# ADC.net
KiCad netlist of a schematic drawn in Altium Designer
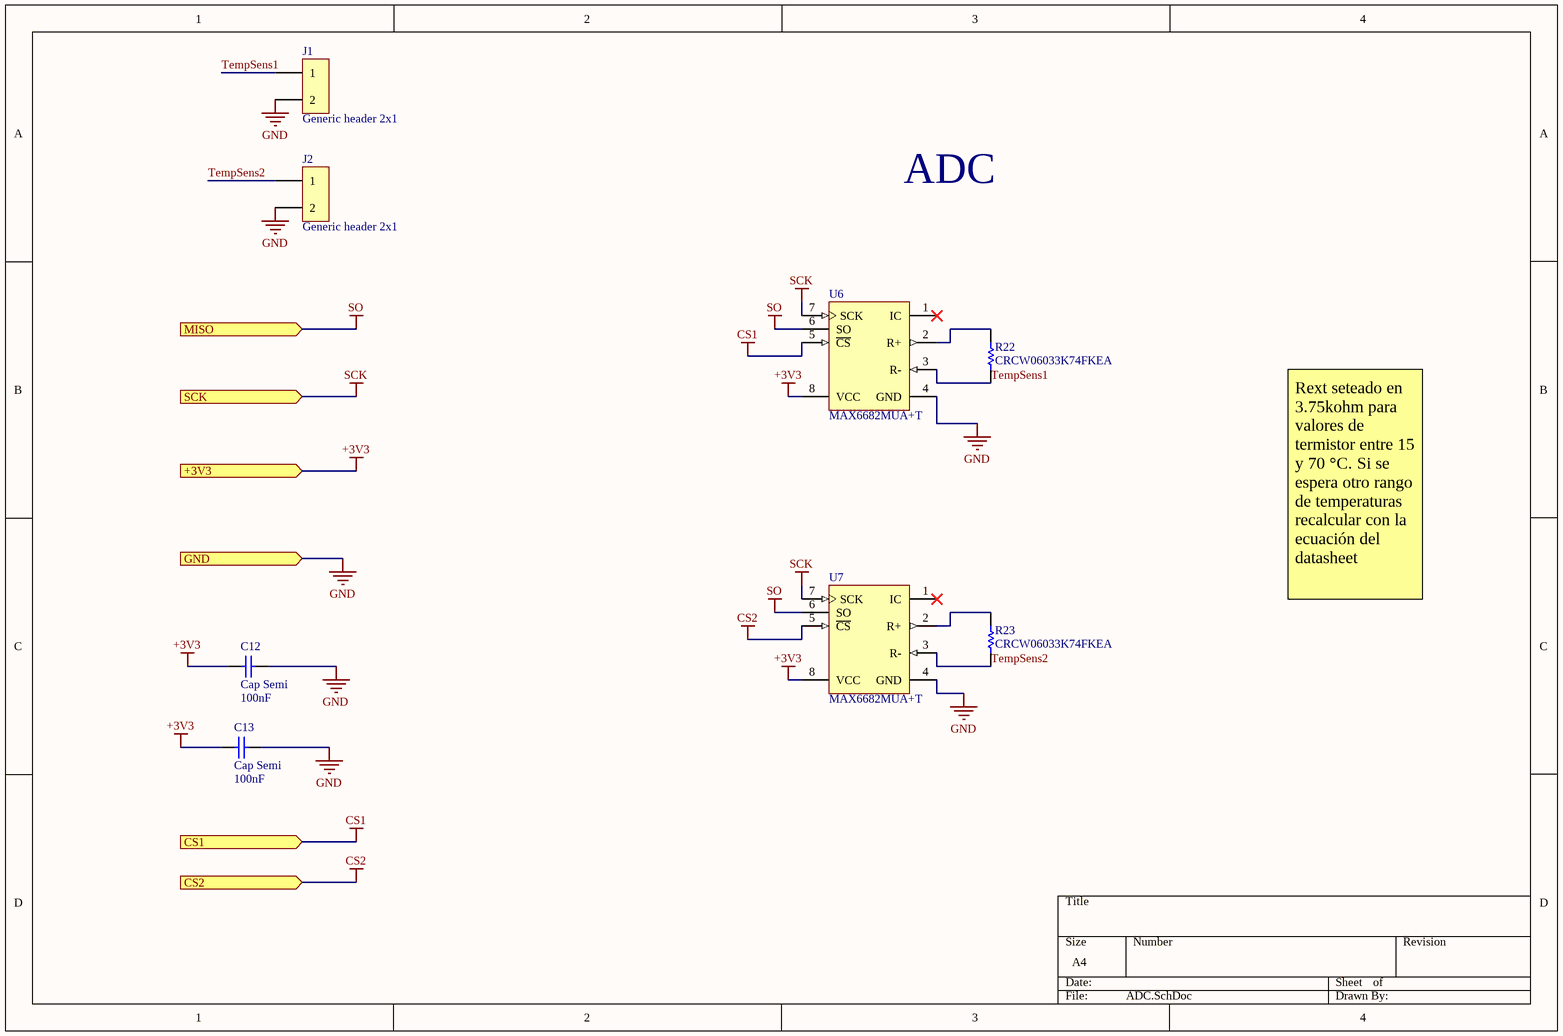
[diagram p0: ADC.SchDoc]

(export (version "E")
  (design (tool "Eeschema 10.0.6"))
  (components
    (comp (ref "C12")
      (value "Cap Semi")
      (footprint "1608[0603]")
      (description "Capacitor (Semiconductor SIM Model)")
      (fields
        (field (name "ALTIUM_VALUE") "100nF")
        (field (name "MANUFACTURER") "Taiyo Yuden")
        (field (name "MANUFACTURER PART NUMBER") "UMK107B104KAHT")
        (field (name "PUBLISHER") "Altium Limited")
      )
      (libsource (lib "Miscellaneous Devices") (part "Cap Semi"))
    )
    (comp (ref "C13")
      (value "Cap Semi")
      (footprint "1608[0603]")
      (description "Capacitor (Semiconductor SIM Model)")
      (fields
        (field (name "ALTIUM_VALUE") "100nF")
        (field (name "MANUFACTURER") "Taiyo Yuden")
        (field (name "MANUFACTURER PART NUMBER") "UMK107B104KAHT")
        (field (name "PUBLISHER") "Altium Limited")
      )
      (libsource (lib "Miscellaneous Devices") (part "Cap Semi"))
    )
    (comp (ref "J1")
      (value "Generic header 2x1")
      (footprint "JST-2x1")
      (description "Generic Header 2pos, 1 row, 2.54 pitch")
      (fields
        (field (name "MANUFACTURER") "CJT(Changjiang Connectors)")
        (field (name "MANUFACTURER PART NUMBER") "A2547WV-2P")
      )
      (libsource (lib "IoWLabsConnectors") (part "Header - 2x1"))
    )
    (comp (ref "J2")
      (value "Generic header 2x1")
      (footprint "JST-2x1")
      (description "Generic Header 2pos, 1 row, 2.54 pitch")
      (fields
        (field (name "MANUFACTURER") "CJT(Changjiang Connectors)")
        (field (name "MANUFACTURER PART NUMBER") "A2547WV-2P")
      )
      (libsource (lib "IoWLabsConnectors") (part "Header - 2x1"))
    )
    (comp (ref "R22")
      (value "CRCW06033K74FKEA")
      (footprint "RESC1609X50X30LL10T20")
      (fields (field (name "MANUFACTURER") "Vishay Dale"))
      (libsource (lib "Altium Content Vault") (part "RES"))
    )
    (comp (ref "R23")
      (value "CRCW06033K74FKEA")
      (footprint "RESC1609X50X30LL10T20")
      (fields (field (name "MANUFACTURER") "Vishay Dale"))
      (libsource (lib "Altium Content Vault") (part "RES"))
    )
    (comp (ref "U6")
      (value "MAX6682MUA+T")
      (footprint "MAXM-U8+1_L")
      (fields (field (name "GENERIC PART NUMBER") "MAX6682"))
      (libsource (lib "Altium Content Vault") (part "MAX6682-U8X1"))
    )
    (comp (ref "U7")
      (value "MAX6682MUA+T")
      (footprint "MAXM-U8+1_L")
      (fields (field (name "GENERIC PART NUMBER") "MAX6682"))
      (libsource (lib "Altium Content Vault") (part "MAX6682-U8X1"))
    )
  )
  (nets
    (net (code "1") (name "+3V3") (class "Default")
      (node (ref "C12") (pin "2") (pinfunction "2_2") (pintype "passive"))
      (node (ref "C13") (pin "2") (pinfunction "2_2") (pintype "passive"))
      (node (ref "U6") (pin "8") (pinfunction "VCC_8") (pintype "power_in"))
      (node (ref "U7") (pin "8") (pinfunction "VCC_8") (pintype "power_in"))
    )
    (net (code "2") (name "/TempSens1") (class "Default")
      (node (ref "J1") (pin "1") (pinfunction "1_1") (pintype "passive"))
      (node (ref "R22") (pin "1") (pinfunction "1_1") (pintype "passive"))
      (node (ref "U6") (pin "3") (pinfunction "R-_3") (pintype "input"))
    )
    (net (code "3") (name "/TempSens2") (class "Default")
      (node (ref "J2") (pin "1") (pinfunction "1_1") (pintype "passive"))
      (node (ref "R23") (pin "1") (pinfunction "1_1") (pintype "passive"))
      (node (ref "U7") (pin "3") (pinfunction "R-_3") (pintype "input"))
    )
    (net (code "4") (name "CS1") (class "Default")
      (node (ref "U6") (pin "5") (pinfunction "~{CS}_5") (pintype "input"))
    )
    (net (code "5") (name "CS2") (class "Default")
      (node (ref "U7") (pin "5") (pinfunction "~{CS}_5") (pintype "input"))
    )
    (net (code "6") (name "GND") (class "Default")
      (node (ref "C12") (pin "1") (pinfunction "1_1") (pintype "passive"))
      (node (ref "C13") (pin "1") (pinfunction "1_1") (pintype "passive"))
      (node (ref "J1") (pin "2") (pinfunction "2_2") (pintype "passive"))
      (node (ref "J2") (pin "2") (pinfunction "2_2") (pintype "passive"))
      (node (ref "U6") (pin "4") (pinfunction "GND_4") (pintype "power_in"))
      (node (ref "U7") (pin "4") (pinfunction "GND_4") (pintype "power_in"))
    )
    (net (code "7") (name "Net-(U6-R+)") (class "Default")
      (node (ref "R22") (pin "2") (pinfunction "2_2") (pintype "passive"))
      (node (ref "U6") (pin "2") (pinfunction "R+_2") (pintype "output"))
    )
    (net (code "8") (name "Net-(U7-R+)") (class "Default")
      (node (ref "R23") (pin "2") (pinfunction "2_2") (pintype "passive"))
      (node (ref "U7") (pin "2") (pinfunction "R+_2") (pintype "output"))
    )
    (net (code "9") (name "SCK") (class "Default")
      (node (ref "U6") (pin "7") (pinfunction "SCK_7") (pintype "input"))
      (node (ref "U7") (pin "7") (pinfunction "SCK_7") (pintype "input"))
    )
    (net (code "10") (name "SO") (class "Default")
      (node (ref "U6") (pin "6") (pinfunction "SO_6") (pintype "tri_state"))
      (node (ref "U7") (pin "6") (pinfunction "SO_6") (pintype "tri_state"))
    )
    (net (code "11") (name "unconnected-(U6-IC-Pad1)") (class "Default")
      (node (ref "U6") (pin "1") (pinfunction "IC_1") (pintype "passive+no_connect"))
    )
    (net (code "12") (name "unconnected-(U7-IC-Pad1)") (class "Default")
      (node (ref "U7") (pin "1") (pinfunction "IC_1") (pintype "passive+no_connect"))
    )
  )
)
